# led_controller.net
KiCad netlist of a schematic drawn in EAGLE
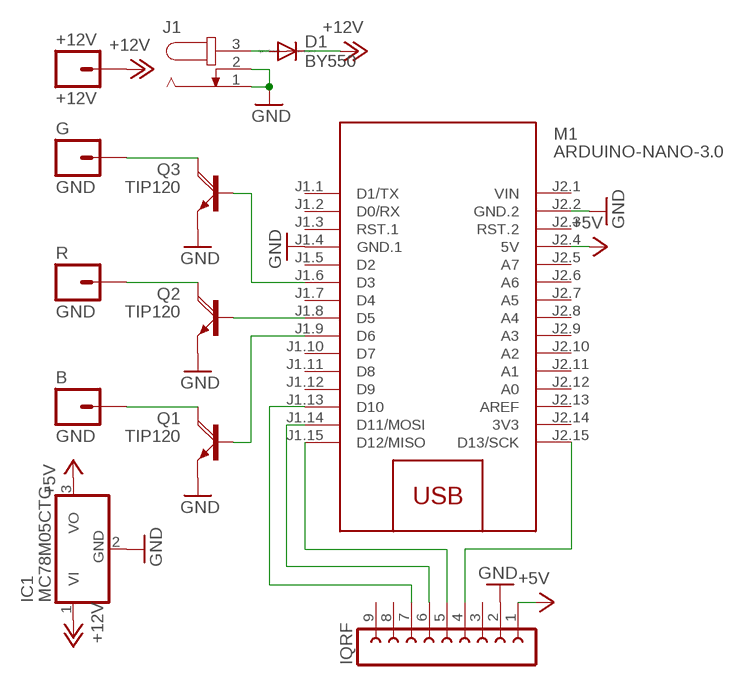
[diagram p0: schematic, sheet 1]

(export (version "E")
  (design (tool "Eeschema 10.0.6"))
  (components
    (comp (ref "+12V")
      (value "+12V")
      (footprint "eagle-import:1X01")
      (libsource (lib "eagle-import") (part "M01PTH"))
    )
    (comp (ref "B")
      (value "GND")
      (footprint "eagle-import:1X01")
      (libsource (lib "eagle-import") (part "M01PTH"))
    )
    (comp (ref "D1")
      (value "BY550")
      (footprint "eagle-import:DO27-15")
      (libsource (lib "eagle-import") (part "BY550"))
    )
    (comp (ref "G")
      (value "GND")
      (footprint "eagle-import:1X01")
      (libsource (lib "eagle-import") (part "M01PTH"))
    )
    (comp (ref "IC1")
      (value "MC78M05CTG")
      (footprint "eagle-import:TO220H")
      (libsource (lib "eagle-import") (part "78T05"))
    )
    (comp (ref "IQRF")
      (value "FE09-1")
      (footprint "eagle-import:FE09")
      (libsource (lib "eagle-import") (part "FE09-1"))
    )
    (comp (ref "J1")
      (value "JACK-PLUG1")
      (footprint "eagle-import:SPC4078")
      (libsource (lib "eagle-import") (part "JACK-PLUG1"))
    )
    (comp (ref "M1")
      (value "ARDUINO-NANO-3.0")
      (footprint "eagle-import:ARDUINO-NANO-3.0")
      (libsource (lib "eagle-import") (part "ARDUINO-NANO-3.0"))
    )
    (comp (ref "Q1")
      (value "TIP120")
      (footprint "eagle-import:TO220AH")
      (libsource (lib "eagle-import") (part "TIP120"))
    )
    (comp (ref "Q2")
      (value "TIP120")
      (footprint "eagle-import:TO220AH")
      (libsource (lib "eagle-import") (part "TIP120"))
    )
    (comp (ref "Q3")
      (value "TIP120")
      (footprint "eagle-import:TO220AH")
      (libsource (lib "eagle-import") (part "TIP120"))
    )
    (comp (ref "R")
      (value "GND")
      (footprint "eagle-import:1X01")
      (libsource (lib "eagle-import") (part "M01PTH"))
    )
  )
  (nets
    (net (code "1") (name "+5V") (class "Default")
      (node (ref "IC1") (pin "3") (pinfunction "VO_3") (pintype "passive"))
      (node (ref "IQRF") (pin "1") (pinfunction "1_1") (pintype "passive"))
      (node (ref "M1") (pin "J2.4") (pinfunction "5V_J2.4") (pintype "power_in"))
    )
    (net (code "2") (name "+12V") (class "Default")
      (node (ref "+12V") (pin "1") (pinfunction "1_1") (pintype "passive"))
      (node (ref "D1") (pin "C") (pinfunction "C_C") (pintype "passive"))
      (node (ref "IC1") (pin "1") (pinfunction "VI_1") (pintype "input"))
    )
    (net (code "3") (name "/3V3") (class "Default")
      (node (ref "M1") (pin "J2.14") (pinfunction "3V3_J2.14") (pintype "power_in"))
    )
    (net (code "4") (name "/VIN") (class "Default")
      (node (ref "M1") (pin "J2.1") (pinfunction "VIN_J2.1") (pintype "power_in"))
    )
    (net (code "5") (name "GND") (class "Default")
      (node (ref "IC1") (pin "2") (pinfunction "GND_2") (pintype "passive"))
      (node (ref "IQRF") (pin "2") (pinfunction "2_2") (pintype "passive"))
      (node (ref "J1") (pin "1") (pinfunction "1_1") (pintype "passive"))
      (node (ref "J1") (pin "2") (pinfunction "2_2") (pintype "passive"))
      (node (ref "M1") (pin "J1.4") (pinfunction "GND.1_J1.4") (pintype "power_in"))
      (node (ref "M1") (pin "J2.2") (pinfunction "GND.2_J2.2") (pintype "power_in"))
      (node (ref "Q1") (pin "E") (pinfunction "E_E") (pintype "passive"))
      (node (ref "Q2") (pin "E") (pinfunction "E_E") (pintype "passive"))
      (node (ref "Q3") (pin "E") (pinfunction "E_E") (pintype "passive"))
    )
    (net (code "6") (name "Net-(B-Pad1)") (class "Default")
      (node (ref "B") (pin "1") (pinfunction "1_1") (pintype "passive"))
      (node (ref "Q1") (pin "C") (pinfunction "C_C") (pintype "passive"))
    )
    (net (code "7") (name "Net-(D1-PadA)") (class "Default")
      (node (ref "D1") (pin "A") (pinfunction "A_A") (pintype "passive"))
      (node (ref "J1") (pin "3") (pinfunction "3_3") (pintype "passive"))
    )
    (net (code "8") (name "Net-(G-Pad1)") (class "Default")
      (node (ref "G") (pin "1") (pinfunction "1_1") (pintype "passive"))
      (node (ref "Q3") (pin "C") (pinfunction "C_C") (pintype "passive"))
    )
    (net (code "9") (name "Net-(M1-D3)") (class "Default")
      (node (ref "M1") (pin "J1.6") (pinfunction "D3_J1.6") (pintype "bidirectional"))
      (node (ref "Q3") (pin "B") (pinfunction "B_B") (pintype "passive"))
    )
    (net (code "10") (name "Net-(M1-D5)") (class "Default")
      (node (ref "M1") (pin "J1.8") (pinfunction "D5_J1.8") (pintype "bidirectional"))
      (node (ref "Q2") (pin "B") (pinfunction "B_B") (pintype "passive"))
    )
    (net (code "11") (name "Net-(M1-D6)") (class "Default")
      (node (ref "M1") (pin "J1.9") (pinfunction "D6_J1.9") (pintype "bidirectional"))
      (node (ref "Q1") (pin "B") (pinfunction "B_B") (pintype "passive"))
    )
    (net (code "12") (name "Net-(M1-D10)") (class "Default")
      (node (ref "IQRF") (pin "7") (pinfunction "7_7") (pintype "passive"))
      (node (ref "M1") (pin "J1.13") (pinfunction "D10_J1.13") (pintype "bidirectional"))
    )
    (net (code "13") (name "Net-(M1-D11{slash}MOSI)") (class "Default")
      (node (ref "IQRF") (pin "6") (pinfunction "6_6") (pintype "passive"))
      (node (ref "M1") (pin "J1.14") (pinfunction "D11/MOSI_J1.14") (pintype "bidirectional"))
    )
    (net (code "14") (name "Net-(M1-D12{slash}MISO)") (class "Default")
      (node (ref "IQRF") (pin "5") (pinfunction "5_5") (pintype "passive"))
      (node (ref "M1") (pin "J1.15") (pinfunction "D12/MISO_J1.15") (pintype "bidirectional"))
    )
    (net (code "15") (name "Net-(M1-D13{slash}SCK)") (class "Default")
      (node (ref "IQRF") (pin "4") (pinfunction "4_4") (pintype "passive"))
      (node (ref "M1") (pin "J2.15") (pinfunction "D13/SCK_J2.15") (pintype "bidirectional"))
    )
    (net (code "16") (name "Net-(Q2-PadC)") (class "Default")
      (node (ref "Q2") (pin "C") (pinfunction "C_C") (pintype "passive"))
      (node (ref "R") (pin "1") (pinfunction "1_1") (pintype "passive"))
    )
    (net (code "17") (name "unconnected-(IQRF-Pad3)") (class "Default")
      (node (ref "IQRF") (pin "3") (pinfunction "3_3") (pintype "passive"))
    )
    (net (code "18") (name "unconnected-(IQRF-Pad8)") (class "Default")
      (node (ref "IQRF") (pin "8") (pinfunction "8_8") (pintype "passive"))
    )
    (net (code "19") (name "unconnected-(IQRF-Pad9)") (class "Default")
      (node (ref "IQRF") (pin "9") (pinfunction "9_9") (pintype "passive"))
    )
    (net (code "20") (name "unconnected-(M1-A0-PadJ2.12)") (class "Default")
      (node (ref "M1") (pin "J2.12") (pinfunction "A0_J2.12") (pintype "bidirectional"))
    )
    (net (code "21") (name "unconnected-(M1-A1-PadJ2.11)") (class "Default")
      (node (ref "M1") (pin "J2.11") (pinfunction "A1_J2.11") (pintype "bidirectional"))
    )
    (net (code "22") (name "unconnected-(M1-A2-PadJ2.10)") (class "Default")
      (node (ref "M1") (pin "J2.10") (pinfunction "A2_J2.10") (pintype "bidirectional"))
    )
    (net (code "23") (name "unconnected-(M1-A3-PadJ2.9)") (class "Default")
      (node (ref "M1") (pin "J2.9") (pinfunction "A3_J2.9") (pintype "bidirectional"))
    )
    (net (code "24") (name "unconnected-(M1-A4-PadJ2.8)") (class "Default")
      (node (ref "M1") (pin "J2.8") (pinfunction "A4_J2.8") (pintype "bidirectional"))
    )
    (net (code "25") (name "unconnected-(M1-A5-PadJ2.7)") (class "Default")
      (node (ref "M1") (pin "J2.7") (pinfunction "A5_J2.7") (pintype "bidirectional"))
    )
    (net (code "26") (name "unconnected-(M1-A6-PadJ2.6)") (class "Default")
      (node (ref "M1") (pin "J2.6") (pinfunction "A6_J2.6") (pintype "bidirectional"))
    )
    (net (code "27") (name "unconnected-(M1-A7-PadJ2.5)") (class "Default")
      (node (ref "M1") (pin "J2.5") (pinfunction "A7_J2.5") (pintype "bidirectional"))
    )
    (net (code "28") (name "unconnected-(M1-AREF-PadJ2.13)") (class "Default")
      (node (ref "M1") (pin "J2.13") (pinfunction "AREF_J2.13") (pintype "bidirectional"))
    )
    (net (code "29") (name "unconnected-(M1-D0{slash}RX-PadJ1.2)") (class "Default")
      (node (ref "M1") (pin "J1.2") (pinfunction "D0/RX_J1.2") (pintype "bidirectional"))
    )
    (net (code "30") (name "unconnected-(M1-D1{slash}TX-PadJ1.1)") (class "Default")
      (node (ref "M1") (pin "J1.1") (pinfunction "D1/TX_J1.1") (pintype "bidirectional"))
    )
    (net (code "31") (name "unconnected-(M1-D2-PadJ1.5)") (class "Default")
      (node (ref "M1") (pin "J1.5") (pinfunction "D2_J1.5") (pintype "bidirectional"))
    )
    (net (code "32") (name "unconnected-(M1-D4-PadJ1.7)") (class "Default")
      (node (ref "M1") (pin "J1.7") (pinfunction "D4_J1.7") (pintype "bidirectional"))
    )
    (net (code "33") (name "unconnected-(M1-D7-PadJ1.10)") (class "Default")
      (node (ref "M1") (pin "J1.10") (pinfunction "D7_J1.10") (pintype "bidirectional"))
    )
    (net (code "34") (name "unconnected-(M1-D8-PadJ1.11)") (class "Default")
      (node (ref "M1") (pin "J1.11") (pinfunction "D8_J1.11") (pintype "bidirectional"))
    )
    (net (code "35") (name "unconnected-(M1-D9-PadJ1.12)") (class "Default")
      (node (ref "M1") (pin "J1.12") (pinfunction "D9_J1.12") (pintype "bidirectional"))
    )
    (net (code "36") (name "unconnected-(M1-RST.1-PadJ1.3)") (class "Default")
      (node (ref "M1") (pin "J1.3") (pinfunction "RST.1_J1.3") (pintype "bidirectional"))
    )
    (net (code "37") (name "unconnected-(M1-RST.2-PadJ2.3)") (class "Default")
      (node (ref "M1") (pin "J2.3") (pinfunction "RST.2_J2.3") (pintype "bidirectional"))
    )
  )
)
